# CON_PCIe_X4.net
KiCad netlist of a schematic drawn in Altium Designer
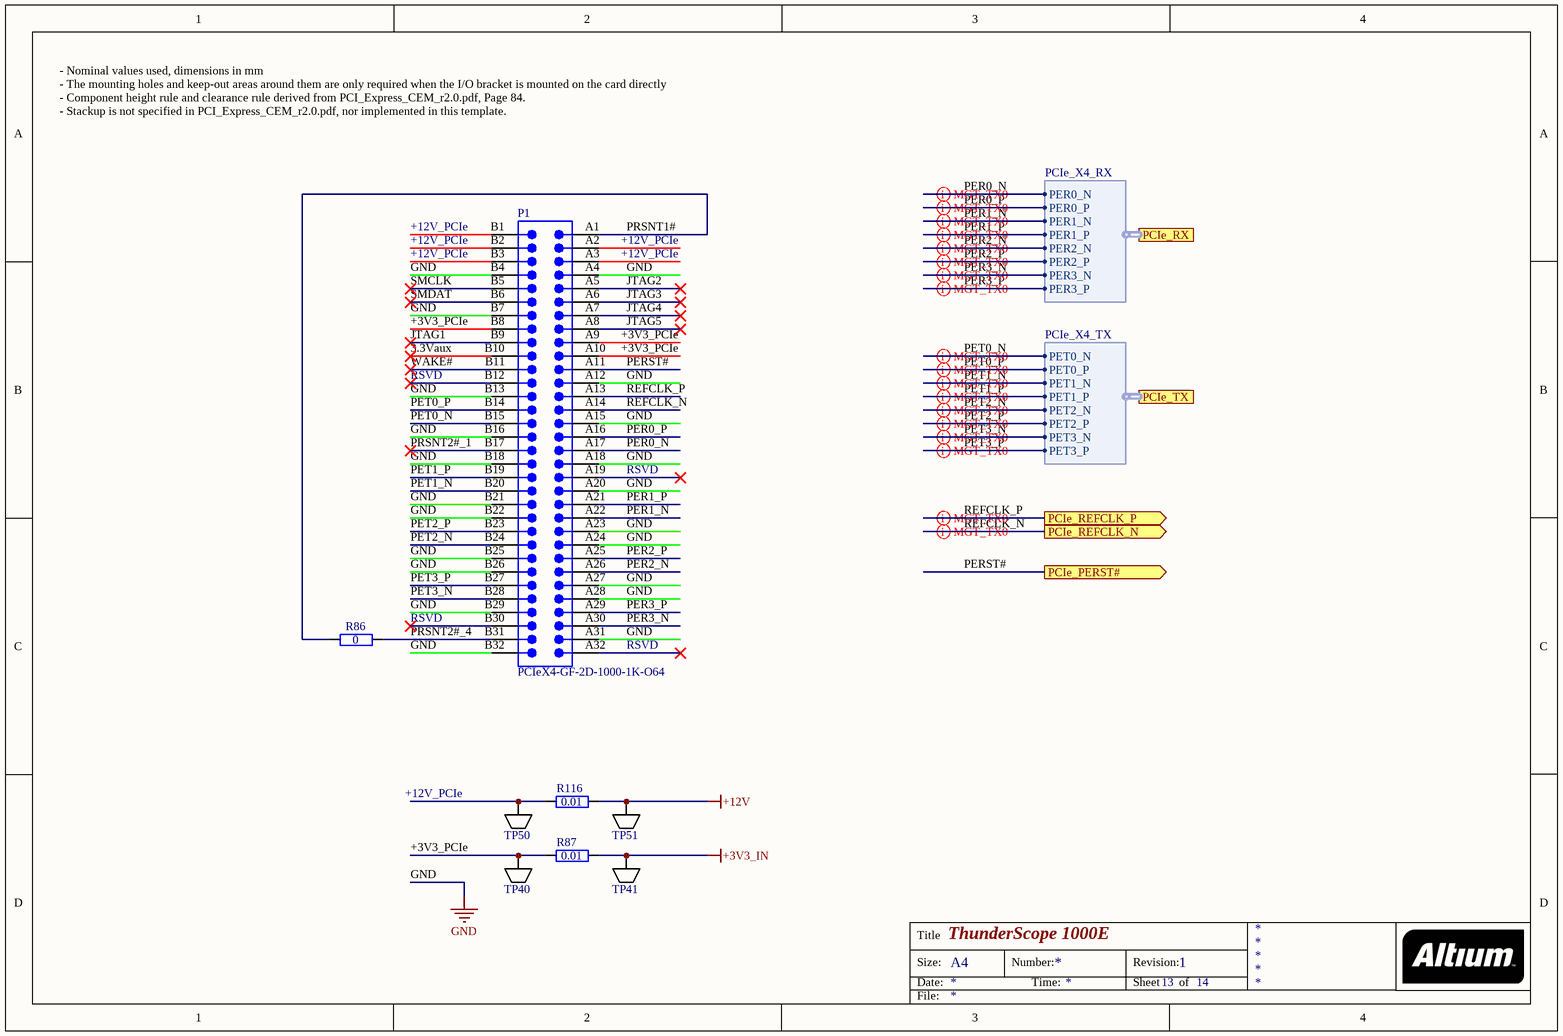
[diagram p0: CON_PCIe_X4.SchDoc]

(export (version "E")
  (design (tool "Eeschema 10.0.6"))
  (components
    (comp (ref "P1")
      (value "PCIeX4-GF-2D-1000-1K-O64")
      (footprint "PCIeX4-GF-2D-1000-1K-O64")
      (description "Golden finger, PCIeX4, Dual, Opposite, Pitch 1mm, 64-Position")
      (fields (field (name "PUBLISHER") "Altium"))
      (libsource (lib "Altium Content Vault") (part "PCIeX4-GF-2D-1000-1K-O64"))
    )
    (comp (ref "R86")
      (value "0")
      (footprint "GEN_R_0402")
      (fields
        (field (name "MANUFACTURER") "Yageo")
        (field (name "MANUFACTURER PART NUMBER") "RC0402JR-070RL")
      )
      (libsource (lib "DSO") (part "RES 0 OHM 1/16W 0402"))
    )
    (comp (ref "R87")
      (value "0.01")
      (footprint "GEN_R_0603")
      (fields
        (field (name "TOLERANCE") "1%")
        (field (name "HOUSE PART NUMBER") "R-0.01-0603-1%-001")
        (field (name "MANUFACTURER") "Susumu")
      )
      (libsource (lib "DSO") (part "RES 0.01 OHM 1% 1/4W 0603"))
    )
    (comp (ref "R116")
      (value "0.01")
      (footprint "GEN_R_0603")
      (fields
        (field (name "TOLERANCE") "1%")
        (field (name "HOUSE PART NUMBER") "R-0.01-0603-1%-001")
        (field (name "MANUFACTURER") "Susumu")
      )
      (libsource (lib "DSO") (part "RES 0.01 OHM 1% 1/4W 0603"))
    )
    (comp (ref "TP40")
      (value "5015")
      (footprint "KEY_5015")
      (fields (field (name "MANUFACTURER") "Keystone Electronics"))
      (libsource (lib "DSO") (part "TP KEYSTONE 5015"))
    )
    (comp (ref "TP41")
      (value "5015")
      (footprint "KEY_5015")
      (fields (field (name "MANUFACTURER") "Keystone Electronics"))
      (libsource (lib "DSO") (part "TP KEYSTONE 5015"))
    )
    (comp (ref "TP50")
      (value "5015")
      (footprint "KEY_5015")
      (fields (field (name "MANUFACTURER") "Keystone Electronics"))
      (libsource (lib "DSO") (part "TP KEYSTONE 5015"))
    )
    (comp (ref "TP51")
      (value "5015")
      (footprint "KEY_5015")
      (fields (field (name "MANUFACTURER") "Keystone Electronics"))
      (libsource (lib "DSO") (part "TP KEYSTONE 5015"))
    )
  )
  (nets
    (net (code "3") (name "+3V3_IN") (class "Default")
      (node (ref "R87") (pin "2") (pinfunction "2_2") (pintype "passive"))
      (node (ref "TP41") (pin "1") (pinfunction "1_1") (pintype "passive"))
    )
    (net (code "4") (name "+12V") (class "Default")
      (node (ref "R116") (pin "2") (pinfunction "2_2") (pintype "passive"))
      (node (ref "TP51") (pin "1") (pinfunction "1_1") (pintype "passive"))
    )
    (net (code "5") (name "/+3V3_PCIe") (class "Default")
      (node (ref "P1") (pin "A10") (pinfunction "A10_A10") (pintype "passive"))
      (node (ref "P1") (pin "A9") (pinfunction "A9_A9") (pintype "passive"))
      (node (ref "P1") (pin "B8") (pinfunction "B8_B8") (pintype "passive"))
      (node (ref "R87") (pin "1") (pinfunction "1_1") (pintype "passive"))
      (node (ref "TP40") (pin "1") (pinfunction "1_1") (pintype "passive"))
    )
    (net (code "6") (name "/+12V_PCIe") (class "Default")
      (node (ref "P1") (pin "A2") (pinfunction "A2_A2") (pintype "passive"))
      (node (ref "P1") (pin "A3") (pinfunction "A3_A3") (pintype "passive"))
      (node (ref "P1") (pin "B1") (pinfunction "B1_B1") (pintype "passive"))
      (node (ref "P1") (pin "B2") (pinfunction "B2_B2") (pintype "passive"))
      (node (ref "P1") (pin "B3") (pinfunction "B3_B3") (pintype "passive"))
      (node (ref "R116") (pin "1") (pinfunction "1_1") (pintype "passive"))
      (node (ref "TP50") (pin "1") (pinfunction "1_1") (pintype "passive"))
    )
    (net (code "7") (name "/3.3Vaux") (class "Default")
      (node (ref "P1") (pin "B10") (pinfunction "B10_B10") (pintype "passive+no_connect"))
    )
    (net (code "8") (name "/JTAG1") (class "Default")
      (node (ref "P1") (pin "B9") (pinfunction "B9_B9") (pintype "passive+no_connect"))
    )
    (net (code "9") (name "/JTAG2") (class "Default")
      (node (ref "P1") (pin "A5") (pinfunction "A5_A5") (pintype "passive+no_connect"))
    )
    (net (code "10") (name "/JTAG3") (class "Default")
      (node (ref "P1") (pin "A6") (pinfunction "A6_A6") (pintype "passive+no_connect"))
    )
    (net (code "11") (name "/JTAG4") (class "Default")
      (node (ref "P1") (pin "A7") (pinfunction "A7_A7") (pintype "passive+no_connect"))
    )
    (net (code "12") (name "/JTAG5") (class "Default")
      (node (ref "P1") (pin "A8") (pinfunction "A8_A8") (pintype "passive+no_connect"))
    )
    (net (code "13") (name "/PER0_N") (class "Default")
      (node (ref "P1") (pin "A17") (pinfunction "A17_A17") (pintype "passive"))
    )
    (net (code "14") (name "/PER0_P") (class "Default")
      (node (ref "P1") (pin "A16") (pinfunction "A16_A16") (pintype "passive"))
    )
    (net (code "15") (name "/PER1_N") (class "Default")
      (node (ref "P1") (pin "A22") (pinfunction "A22_A22") (pintype "passive"))
    )
    (net (code "16") (name "/PER1_P") (class "Default")
      (node (ref "P1") (pin "A21") (pinfunction "A21_A21") (pintype "passive"))
    )
    (net (code "17") (name "/PER2_N") (class "Default")
      (node (ref "P1") (pin "A26") (pinfunction "A26_A26") (pintype "passive"))
    )
    (net (code "18") (name "/PER2_P") (class "Default")
      (node (ref "P1") (pin "A25") (pinfunction "A25_A25") (pintype "passive"))
    )
    (net (code "19") (name "/PER3_N") (class "Default")
      (node (ref "P1") (pin "A30") (pinfunction "A30_A30") (pintype "passive"))
    )
    (net (code "20") (name "/PER3_P") (class "Default")
      (node (ref "P1") (pin "A29") (pinfunction "A29_A29") (pintype "passive"))
    )
    (net (code "21") (name "/PERST#") (class "Default")
      (node (ref "P1") (pin "A11") (pinfunction "A11_A11") (pintype "passive"))
    )
    (net (code "22") (name "/PET0_N") (class "Default")
      (node (ref "P1") (pin "B15") (pinfunction "B15_B15") (pintype "passive"))
    )
    (net (code "23") (name "/PET0_P") (class "Default")
      (node (ref "P1") (pin "B14") (pinfunction "B14_B14") (pintype "passive"))
    )
    (net (code "24") (name "/PET1_N") (class "Default")
      (node (ref "P1") (pin "B20") (pinfunction "B20_B20") (pintype "passive"))
    )
    (net (code "25") (name "/PET1_P") (class "Default")
      (node (ref "P1") (pin "B19") (pinfunction "B19_B19") (pintype "passive"))
    )
    (net (code "26") (name "/PET2_N") (class "Default")
      (node (ref "P1") (pin "B24") (pinfunction "B24_B24") (pintype "passive"))
    )
    (net (code "27") (name "/PET2_P") (class "Default")
      (node (ref "P1") (pin "B23") (pinfunction "B23_B23") (pintype "passive"))
    )
    (net (code "28") (name "/PET3_N") (class "Default")
      (node (ref "P1") (pin "B28") (pinfunction "B28_B28") (pintype "passive"))
    )
    (net (code "29") (name "/PET3_P") (class "Default")
      (node (ref "P1") (pin "B27") (pinfunction "B27_B27") (pintype "passive"))
    )
    (net (code "30") (name "/PRSNT1#") (class "Default")
      (node (ref "P1") (pin "A1") (pinfunction "A1_A1") (pintype "passive"))
      (node (ref "R86") (pin "1") (pinfunction "1_1") (pintype "passive"))
    )
    (net (code "31") (name "/PRSNT2#_1") (class "Default")
      (node (ref "P1") (pin "B17") (pinfunction "B17_B17") (pintype "passive+no_connect"))
    )
    (net (code "32") (name "/PRSNT2#_4") (class "Default")
      (node (ref "P1") (pin "B31") (pinfunction "B31_B31") (pintype "passive"))
      (node (ref "R86") (pin "2") (pinfunction "2_2") (pintype "passive"))
    )
    (net (code "33") (name "/REFCLK_N") (class "Default")
      (node (ref "P1") (pin "A14") (pinfunction "A14_A14") (pintype "passive"))
    )
    (net (code "34") (name "/REFCLK_P") (class "Default")
      (node (ref "P1") (pin "A13") (pinfunction "A13_A13") (pintype "passive"))
    )
    (net (code "35") (name "/SMCLK") (class "Default")
      (node (ref "P1") (pin "B5") (pinfunction "B5_B5") (pintype "passive+no_connect"))
    )
    (net (code "36") (name "/SMDAT") (class "Default")
      (node (ref "P1") (pin "B6") (pinfunction "B6_B6") (pintype "passive+no_connect"))
    )
    (net (code "37") (name "/WAKE#") (class "Default")
      (node (ref "P1") (pin "B11") (pinfunction "B11_B11") (pintype "passive+no_connect"))
    )
    (net (code "40") (name "GND") (class "Default")
      (node (ref "P1") (pin "A12") (pinfunction "A12_A12") (pintype "passive"))
      (node (ref "P1") (pin "A15") (pinfunction "A15_A15") (pintype "passive"))
      (node (ref "P1") (pin "A18") (pinfunction "A18_A18") (pintype "passive"))
      (node (ref "P1") (pin "A20") (pinfunction "A20_A20") (pintype "passive"))
      (node (ref "P1") (pin "A23") (pinfunction "A23_A23") (pintype "passive"))
      (node (ref "P1") (pin "A24") (pinfunction "A24_A24") (pintype "passive"))
      (node (ref "P1") (pin "A27") (pinfunction "A27_A27") (pintype "passive"))
      (node (ref "P1") (pin "A28") (pinfunction "A28_A28") (pintype "passive"))
      (node (ref "P1") (pin "A31") (pinfunction "A31_A31") (pintype "passive"))
      (node (ref "P1") (pin "A4") (pinfunction "A4_A4") (pintype "passive"))
      (node (ref "P1") (pin "B13") (pinfunction "B13_B13") (pintype "passive"))
      (node (ref "P1") (pin "B16") (pinfunction "B16_B16") (pintype "passive"))
      (node (ref "P1") (pin "B18") (pinfunction "B18_B18") (pintype "passive"))
      (node (ref "P1") (pin "B21") (pinfunction "B21_B21") (pintype "passive"))
      (node (ref "P1") (pin "B22") (pinfunction "B22_B22") (pintype "passive"))
      (node (ref "P1") (pin "B25") (pinfunction "B25_B25") (pintype "passive"))
      (node (ref "P1") (pin "B26") (pinfunction "B26_B26") (pintype "passive"))
      (node (ref "P1") (pin "B29") (pinfunction "B29_B29") (pintype "passive"))
      (node (ref "P1") (pin "B32") (pinfunction "B32_B32") (pintype "passive"))
      (node (ref "P1") (pin "B4") (pinfunction "B4_B4") (pintype "passive"))
      (node (ref "P1") (pin "B7") (pinfunction "B7_B7") (pintype "passive"))
    )
    (net (code "41") (name "unconnected-(P1-PadA19)") (class "Default")
      (node (ref "P1") (pin "A19") (pinfunction "A19_A19") (pintype "passive+no_connect"))
    )
    (net (code "42") (name "unconnected-(P1-PadA32)") (class "Default")
      (node (ref "P1") (pin "A32") (pinfunction "A32_A32") (pintype "passive+no_connect"))
    )
    (net (code "43") (name "unconnected-(P1-PadB12)") (class "Default")
      (node (ref "P1") (pin "B12") (pinfunction "B12_B12") (pintype "passive+no_connect"))
    )
    (net (code "44") (name "unconnected-(P1-PadB30)") (class "Default")
      (node (ref "P1") (pin "B30") (pinfunction "B30_B30") (pintype "passive+no_connect"))
    )
  )
)
